# MIPI_CSI_0_and_1_Connectors.net
KiCad netlist of a schematic drawn in Altium Designer
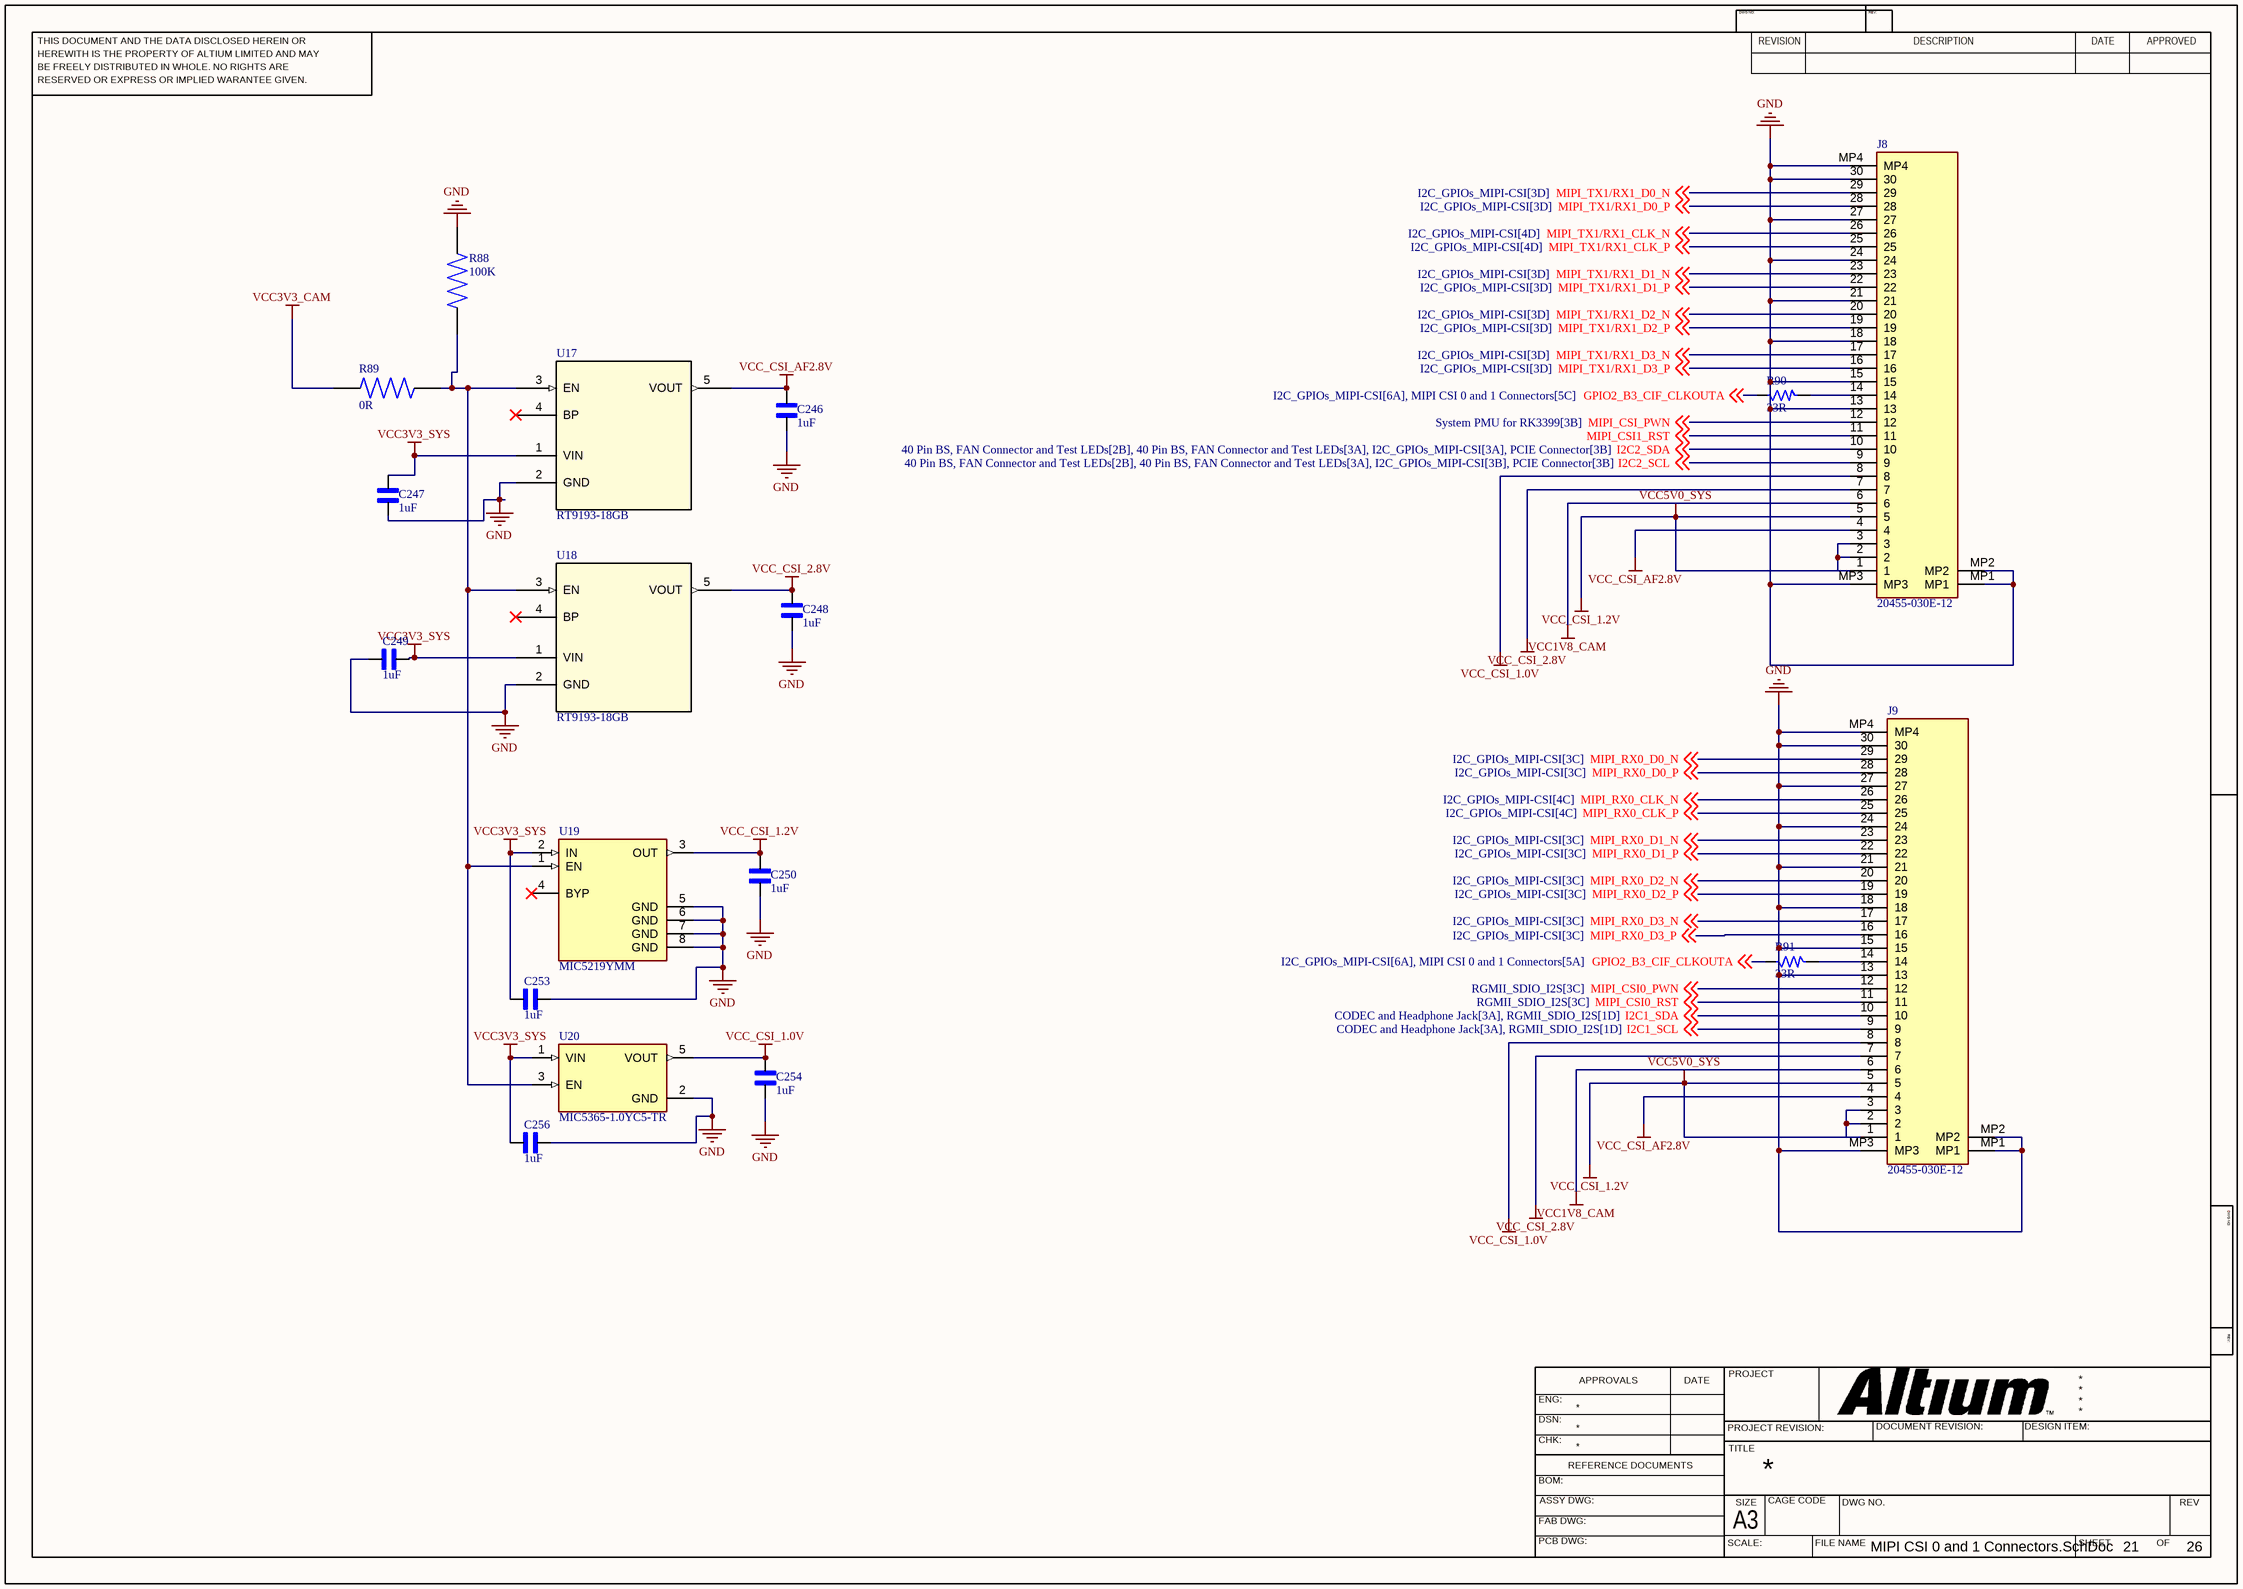
[diagram p0: MIPI CSI 0 and 1 Connectors.SchDoc]

(export (version "E")
  (design (tool "Eeschema 10.0.6"))
  (components
    (comp (ref "C246")
      (value "1uF")
      (footprint "CAPC1005X56N")
      (description "1 ÂµF Â±10% 10V Ceramic Capacitor X5R 0402 (1005 Metric)")
      (fields (field (name "MF") "AVX") (field (name "MP") "0402ZD105KAT4A"))
      (libsource (lib "0402ZD105KAT4A") (part "0402ZD105KAT4A"))
    )
    (comp (ref "C247")
      (value "1uF")
      (footprint "CAPC1005X56N")
      (description "1 ÂµF Â±10% 10V Ceramic Capacitor X5R 0402 (1005 Metric)")
      (fields (field (name "MF") "AVX") (field (name "MP") "0402ZD105KAT4A"))
      (libsource (lib "0402ZD105KAT4A") (part "0402ZD105KAT4A"))
    )
    (comp (ref "C248")
      (value "1uF")
      (footprint "CAPC1005X56N")
      (description "1 ÂµF Â±10% 10V Ceramic Capacitor X5R 0402 (1005 Metric)")
      (fields (field (name "MF") "AVX") (field (name "MP") "0402ZD105KAT4A"))
      (libsource (lib "0402ZD105KAT4A") (part "0402ZD105KAT4A"))
    )
    (comp (ref "C249")
      (value "1uF")
      (footprint "CAPC1005X56N")
      (description "1 ÂµF Â±10% 10V Ceramic Capacitor X5R 0402 (1005 Metric)")
      (fields (field (name "MF") "AVX") (field (name "MP") "0402ZD105KAT4A"))
      (libsource (lib "") (part "0402ZD105KAT4A_1"))
    )
    (comp (ref "C250")
      (value "1uF")
      (footprint "CAPC1005X56N")
      (description "1 ÂµF Â±10% 10V Ceramic Capacitor X5R 0402 (1005 Metric)")
      (fields (field (name "MF") "AVX") (field (name "MP") "0402ZD105KAT4A"))
      (libsource (lib "0402ZD105KAT4A") (part "0402ZD105KAT4A"))
    )
    (comp (ref "C253")
      (value "1uF")
      (footprint "CAPC1005X56N")
      (description "1 ÂµF Â±10% 10V Ceramic Capacitor X5R 0402 (1005 Metric)")
      (fields (field (name "MF") "AVX") (field (name "MP") "0402ZD105KAT4A"))
      (libsource (lib "") (part "0402ZD105KAT4A_1"))
    )
    (comp (ref "C254")
      (value "1uF")
      (footprint "CAPC1005X56N")
      (description "1 ÂµF Â±10% 10V Ceramic Capacitor X5R 0402 (1005 Metric)")
      (fields (field (name "MF") "AVX") (field (name "MP") "0402ZD105KAT4A"))
      (libsource (lib "0402ZD105KAT4A") (part "0402ZD105KAT4A"))
    )
    (comp (ref "C256")
      (value "1uF")
      (footprint "CAPC1005X56N")
      (description "1 ÂµF Â±10% 10V Ceramic Capacitor X5R 0402 (1005 Metric)")
      (fields (field (name "MF") "AVX") (field (name "MP") "0402ZD105KAT4A"))
      (libsource (lib "") (part "0402ZD105KAT4A_1"))
    )
    (comp (ref "J8")
      (value "20455-030E-12")
      (footprint "20455030E12")
      (description "Board Connector, 30 Contact(s), 1 Row(s), Female, Right Angle, Surface Mount Terminal, Receptacle")
      (libsource (lib "20455-030E-12") (part "20455-030E-12"))
    )
    (comp (ref "J9")
      (value "20455-030E-12")
      (footprint "20455030E12")
      (description "Board Connector, 30 Contact(s), 1 Row(s), Female, Right Angle, Surface Mount Terminal, Receptacle")
      (libsource (lib "20455-030E-12") (part "20455-030E-12"))
    )
    (comp (ref "R88")
      (value "100K")
      (footprint "RES_ERA3ARB103V")
      (fields (field (name "MP") "ERA3ARB103V"))
      (libsource (lib "ERA3ARB103V") (part "ERA3ARB103V"))
    )
    (comp (ref "R89")
      (value "0R")
      (footprint "RES_ERJH6G0R00V")
      (fields (field (name "MP") "ERJH6G0R00V"))
      (libsource (lib "ERJH6G0R00V") (part "ERJH6G0R00V"))
    )
    (comp (ref "R90")
      (value "33R")
      (footprint "RESC1608X50N")
      (description "33 Ohms ±1% 0.1W, 1/10W Chip Resistor 0402 (1005 Metric) Automotive AEC-Q200 Thick Film")
      (fields
        (field (name "MANUFACTURER") "Panasonic Electronic Components")
        (field (name "MANUFACTURER PART NUMBER") "ERJ-2RKF33R0X")
      )
      (libsource (lib "RK3399 _Module_Schlib") (part "RES_33R-0.1W-1%-0402"))
    )
    (comp (ref "R91")
      (value "33R")
      (footprint "RESC1608X50N")
      (description "33 Ohms ±1% 0.1W, 1/10W Chip Resistor 0402 (1005 Metric) Automotive AEC-Q200 Thick Film")
      (fields
        (field (name "MANUFACTURER") "Panasonic Electronic Components")
        (field (name "MANUFACTURER PART NUMBER") "ERJ-2RKF33R0X")
      )
      (libsource (lib "RK3399 _Module_Schlib") (part "RES_33R-0.1W-1%-0402"))
    )
    (comp (ref "U17")
      (value "RT9193-18GB")
      (footprint "SOT-23-5_RIT")
      (description "Description")
      (fields (field (name "COPYRIGHT") "Copyright (C) 2026 Ultra Librarian. All rights reserved."))
      (libsource (lib "RT9193-18GB") (part "RT9193-18GB"))
    )
    (comp (ref "U18")
      (value "RT9193-18GB")
      (footprint "SOT-23-5_RIT")
      (description "Description")
      (fields (field (name "COPYRIGHT") "Copyright (C) 2026 Ultra Librarian. All rights reserved."))
      (libsource (lib "RT9193-18GB") (part "RT9193-18GB"))
    )
    (comp (ref "U19")
      (value "MIC5219YMM")
      (footprint "SOP65P490X110-8N")
      (description "MIC5219 Series 500 mA ADJ Output Voltage Surface Mount LDO Regulator - MSOP-8")
      (fields (field (name "MF") "Microchip"))
      (libsource (lib "MIC5219YMM") (part "MIC5219YMM"))
    )
    (comp (ref "U20")
      (value "MIC5365-1.0YC5-TR")
      (footprint "SOT65P210X110-5N")
      (description "Linear Voltage Regulator IC Positive Fixed 1 Output 150mA SC-70-5")
      (fields (field (name "MF") "Microchip"))
      (libsource (lib "MIC5365-1.0YC5-TR") (part "MIC5365-1.0YC5-TR"))
    )
  )
  (nets
    (net (code "1") (name "GND") (class "Default")
      (node (ref "C246") (pin "1") (pinfunction "1_1") (pintype "passive"))
      (node (ref "C247") (pin "1") (pinfunction "1_1") (pintype "passive"))
      (node (ref "C248") (pin "1") (pinfunction "1_1") (pintype "passive"))
      (node (ref "C249") (pin "2") (pinfunction "2_2") (pintype "passive"))
      (node (ref "C250") (pin "1") (pinfunction "1_1") (pintype "passive"))
      (node (ref "C253") (pin "1") (pinfunction "1_1") (pintype "passive"))
      (node (ref "C254") (pin "1") (pinfunction "1_1") (pintype "passive"))
      (node (ref "C256") (pin "1") (pinfunction "1_1") (pintype "passive"))
      (node (ref "J8") (pin "13") (pinfunction "13_13") (pintype "passive"))
      (node (ref "J8") (pin "15") (pinfunction "15_15") (pintype "passive"))
      (node (ref "J8") (pin "18") (pinfunction "18_18") (pintype "passive"))
      (node (ref "J8") (pin "21") (pinfunction "21_21") (pintype "passive"))
      (node (ref "J8") (pin "24") (pinfunction "24_24") (pintype "passive"))
      (node (ref "J8") (pin "27") (pinfunction "27_27") (pintype "passive"))
      (node (ref "J8") (pin "30") (pinfunction "30_30") (pintype "passive"))
      (node (ref "J8") (pin "MP1") (pinfunction "MP1_MP1") (pintype "passive"))
      (node (ref "J8") (pin "MP2") (pinfunction "MP2_MP2") (pintype "passive"))
      (node (ref "J8") (pin "MP3") (pinfunction "MP3_MP3") (pintype "passive"))
      (node (ref "J8") (pin "MP4") (pinfunction "MP4_MP4") (pintype "passive"))
      (node (ref "J9") (pin "13") (pinfunction "13_13") (pintype "passive"))
      (node (ref "J9") (pin "15") (pinfunction "15_15") (pintype "passive"))
      (node (ref "J9") (pin "18") (pinfunction "18_18") (pintype "passive"))
      (node (ref "J9") (pin "21") (pinfunction "21_21") (pintype "passive"))
      (node (ref "J9") (pin "24") (pinfunction "24_24") (pintype "passive"))
      (node (ref "J9") (pin "27") (pinfunction "27_27") (pintype "passive"))
      (node (ref "J9") (pin "30") (pinfunction "30_30") (pintype "passive"))
      (node (ref "J9") (pin "MP1") (pinfunction "MP1_MP1") (pintype "passive"))
      (node (ref "J9") (pin "MP2") (pinfunction "MP2_MP2") (pintype "passive"))
      (node (ref "J9") (pin "MP3") (pinfunction "MP3_MP3") (pintype "passive"))
      (node (ref "J9") (pin "MP4") (pinfunction "MP4_MP4") (pintype "passive"))
      (node (ref "R88") (pin "2") (pinfunction "2_2") (pintype "passive"))
      (node (ref "U17") (pin "2") (pinfunction "GND_2") (pintype "power_in"))
      (node (ref "U18") (pin "2") (pinfunction "GND_2") (pintype "power_in"))
      (node (ref "U19") (pin "5") (pinfunction "GND_5") (pintype "power_in"))
      (node (ref "U19") (pin "6") (pinfunction "GND_6") (pintype "power_in"))
      (node (ref "U19") (pin "7") (pinfunction "GND_7") (pintype "power_in"))
      (node (ref "U19") (pin "8") (pinfunction "GND_8") (pintype "power_in"))
      (node (ref "U20") (pin "2") (pinfunction "GND_2") (pintype "power_in"))
    )
    (net (code "2") (name "GPIO2_B3_CIF_CLKOUTA") (class "Default")
      (node (ref "R90") (pin "1") (pinfunction "1_1") (pintype "passive"))
      (node (ref "R91") (pin "1") (pinfunction "1_1") (pintype "passive"))
    )
    (net (code "3") (name "I2C1_SCL") (class "Default")
      (node (ref "J9") (pin "9") (pinfunction "9_9") (pintype "passive"))
    )
    (net (code "4") (name "I2C1_SDA") (class "Default")
      (node (ref "J9") (pin "10") (pinfunction "10_10") (pintype "passive"))
    )
    (net (code "5") (name "I2C2_SCL") (class "Default")
      (node (ref "J8") (pin "9") (pinfunction "9_9") (pintype "passive"))
    )
    (net (code "6") (name "I2C2_SDA") (class "Default")
      (node (ref "J8") (pin "10") (pinfunction "10_10") (pintype "passive"))
    )
    (net (code "7") (name "MIPI_CSI0_PWN") (class "Default")
      (node (ref "J9") (pin "12") (pinfunction "12_12") (pintype "passive"))
    )
    (net (code "8") (name "MIPI_CSI0_RST") (class "Default")
      (node (ref "J9") (pin "11") (pinfunction "11_11") (pintype "passive"))
    )
    (net (code "9") (name "MIPI_CSI1_RST") (class "Default")
      (node (ref "J8") (pin "11") (pinfunction "11_11") (pintype "passive"))
    )
    (net (code "10") (name "MIPI_CSI_PWN") (class "Default")
      (node (ref "J8") (pin "12") (pinfunction "12_12") (pintype "passive"))
    )
    (net (code "11") (name "MIPI_RX0_CLK_N") (class "Default")
      (node (ref "J9") (pin "26") (pinfunction "26_26") (pintype "passive"))
    )
    (net (code "12") (name "MIPI_RX0_CLK_P") (class "Default")
      (node (ref "J9") (pin "25") (pinfunction "25_25") (pintype "passive"))
    )
    (net (code "13") (name "MIPI_RX0_D0_N") (class "Default")
      (node (ref "J9") (pin "29") (pinfunction "29_29") (pintype "passive"))
    )
    (net (code "14") (name "MIPI_RX0_D0_P") (class "Default")
      (node (ref "J9") (pin "28") (pinfunction "28_28") (pintype "passive"))
    )
    (net (code "15") (name "MIPI_RX0_D1_N") (class "Default")
      (node (ref "J9") (pin "23") (pinfunction "23_23") (pintype "passive"))
    )
    (net (code "16") (name "MIPI_RX0_D1_P") (class "Default")
      (node (ref "J9") (pin "22") (pinfunction "22_22") (pintype "passive"))
    )
    (net (code "17") (name "MIPI_RX0_D2_N") (class "Default")
      (node (ref "J9") (pin "20") (pinfunction "20_20") (pintype "passive"))
    )
    (net (code "18") (name "MIPI_RX0_D2_P") (class "Default")
      (node (ref "J9") (pin "19") (pinfunction "19_19") (pintype "passive"))
    )
    (net (code "19") (name "MIPI_RX0_D3_N") (class "Default")
      (node (ref "J9") (pin "17") (pinfunction "17_17") (pintype "passive"))
    )
    (net (code "20") (name "MIPI_RX0_D3_P") (class "Default")
      (node (ref "J9") (pin "16") (pinfunction "16_16") (pintype "passive"))
    )
    (net (code "21") (name "MIPI_TX1{slash}RX1_CLK_N") (class "Default")
      (node (ref "J8") (pin "26") (pinfunction "26_26") (pintype "passive"))
    )
    (net (code "22") (name "MIPI_TX1{slash}RX1_CLK_P") (class "Default")
      (node (ref "J8") (pin "25") (pinfunction "25_25") (pintype "passive"))
    )
    (net (code "23") (name "MIPI_TX1{slash}RX1_D0_N") (class "Default")
      (node (ref "J8") (pin "29") (pinfunction "29_29") (pintype "passive"))
    )
    (net (code "24") (name "MIPI_TX1{slash}RX1_D0_P") (class "Default")
      (node (ref "J8") (pin "28") (pinfunction "28_28") (pintype "passive"))
    )
    (net (code "25") (name "MIPI_TX1{slash}RX1_D1_N") (class "Default")
      (node (ref "J8") (pin "23") (pinfunction "23_23") (pintype "passive"))
    )
    (net (code "26") (name "MIPI_TX1{slash}RX1_D1_P") (class "Default")
      (node (ref "J8") (pin "22") (pinfunction "22_22") (pintype "passive"))
    )
    (net (code "27") (name "MIPI_TX1{slash}RX1_D2_N") (class "Default")
      (node (ref "J8") (pin "20") (pinfunction "20_20") (pintype "passive"))
    )
    (net (code "28") (name "MIPI_TX1{slash}RX1_D2_P") (class "Default")
      (node (ref "J8") (pin "19") (pinfunction "19_19") (pintype "passive"))
    )
    (net (code "29") (name "MIPI_TX1{slash}RX1_D3_N") (class "Default")
      (node (ref "J8") (pin "17") (pinfunction "17_17") (pintype "passive"))
    )
    (net (code "30") (name "MIPI_TX1{slash}RX1_D3_P") (class "Default")
      (node (ref "J8") (pin "16") (pinfunction "16_16") (pintype "passive"))
    )
    (net (code "31") (name "Net-(J8-Pad14)") (class "Default")
      (node (ref "J8") (pin "14") (pinfunction "14_14") (pintype "passive"))
      (node (ref "R90") (pin "2") (pinfunction "2_2") (pintype "passive"))
    )
    (net (code "32") (name "Net-(J9-Pad14)") (class "Default")
      (node (ref "J9") (pin "14") (pinfunction "14_14") (pintype "passive"))
      (node (ref "R91") (pin "2") (pinfunction "2_2") (pintype "passive"))
    )
    (net (code "33") (name "Net-(U17-EN)") (class "Default")
      (node (ref "R88") (pin "1") (pinfunction "1_1") (pintype "passive"))
      (node (ref "R89") (pin "2") (pinfunction "2_2") (pintype "passive"))
      (node (ref "U17") (pin "3") (pinfunction "EN_3") (pintype "input"))
      (node (ref "U18") (pin "3") (pinfunction "EN_3") (pintype "input"))
      (node (ref "U19") (pin "1") (pinfunction "EN_1") (pintype "input"))
      (node (ref "U20") (pin "3") (pinfunction "EN_3") (pintype "input"))
    )
    (net (code "34") (name "VCC1V8_CAM") (class "Default")
      (node (ref "J8") (pin "6") (pinfunction "6_6") (pintype "passive"))
      (node (ref "J9") (pin "6") (pinfunction "6_6") (pintype "passive"))
    )
    (net (code "35") (name "VCC3V3_CAM") (class "Default")
      (node (ref "R89") (pin "1") (pinfunction "1_1") (pintype "passive"))
    )
    (net (code "36") (name "VCC3V3_SYS") (class "Default")
      (node (ref "C247") (pin "2") (pinfunction "2_2") (pintype "passive"))
      (node (ref "C249") (pin "1") (pinfunction "1_1") (pintype "passive"))
      (node (ref "C253") (pin "2") (pinfunction "2_2") (pintype "passive"))
      (node (ref "C256") (pin "2") (pinfunction "2_2") (pintype "passive"))
      (node (ref "U17") (pin "1") (pinfunction "VIN_1") (pintype "power_in"))
      (node (ref "U18") (pin "1") (pinfunction "VIN_1") (pintype "power_in"))
      (node (ref "U19") (pin "2") (pinfunction "IN_2") (pintype "input"))
      (node (ref "U20") (pin "1") (pinfunction "VIN_1") (pintype "input"))
    )
    (net (code "37") (name "VCC5V0_SYS") (class "Default")
      (node (ref "C250") (pin "2") (pinfunction "2_2") (pintype "passive"))
      (node (ref "J8") (pin "1") (pinfunction "1_1") (pintype "passive"))
      (node (ref "J8") (pin "2") (pinfunction "2_2") (pintype "passive"))
      (node (ref "J8") (pin "3") (pinfunction "3_3") (pintype "passive"))
      (node (ref "J8") (pin "5") (pinfunction "5_5") (pintype "passive"))
      (node (ref "J9") (pin "1") (pinfunction "1_1") (pintype "passive"))
      (node (ref "J9") (pin "2") (pinfunction "2_2") (pintype "passive"))
      (node (ref "J9") (pin "3") (pinfunction "3_3") (pintype "passive"))
      (node (ref "J9") (pin "5") (pinfunction "5_5") (pintype "passive"))
      (node (ref "U19") (pin "3") (pinfunction "OUT_3") (pintype "output"))
    )
    (net (code "38") (name "VCC_CSI_1.0V") (class "Default")
      (node (ref "C254") (pin "2") (pinfunction "2_2") (pintype "passive"))
      (node (ref "J8") (pin "8") (pinfunction "8_8") (pintype "passive"))
      (node (ref "J9") (pin "8") (pinfunction "8_8") (pintype "passive"))
      (node (ref "U20") (pin "5") (pinfunction "VOUT_5") (pintype "output"))
    )
    (net (code "39") (name "VCC_CSI_2.8V") (class "Default")
      (node (ref "C248") (pin "2") (pinfunction "2_2") (pintype "passive"))
      (node (ref "J8") (pin "7") (pinfunction "7_7") (pintype "passive"))
      (node (ref "J9") (pin "7") (pinfunction "7_7") (pintype "passive"))
      (node (ref "U18") (pin "5") (pinfunction "VOUT_5") (pintype "output"))
    )
    (net (code "40") (name "VCC_CSI_AF2.8V") (class "Default")
      (node (ref "C246") (pin "2") (pinfunction "2_2") (pintype "passive"))
      (node (ref "J8") (pin "4") (pinfunction "4_4") (pintype "passive"))
      (node (ref "J9") (pin "4") (pinfunction "4_4") (pintype "passive"))
      (node (ref "U17") (pin "5") (pinfunction "VOUT_5") (pintype "output"))
    )
    (net (code "41") (name "unconnected-(U17-BP-Pad4)") (class "Default")
      (node (ref "U17") (pin "4") (pinfunction "BP_4") (pintype "passive+no_connect"))
    )
    (net (code "42") (name "unconnected-(U18-BP-Pad4)") (class "Default")
      (node (ref "U18") (pin "4") (pinfunction "BP_4") (pintype "passive+no_connect"))
    )
    (net (code "43") (name "unconnected-(U19-BYP-Pad4)") (class "Default")
      (node (ref "U19") (pin "4") (pinfunction "BYP_4") (pintype "passive+no_connect"))
    )
  )
)
